# A.net
KiCad netlist of a schematic drawn in EAGLE
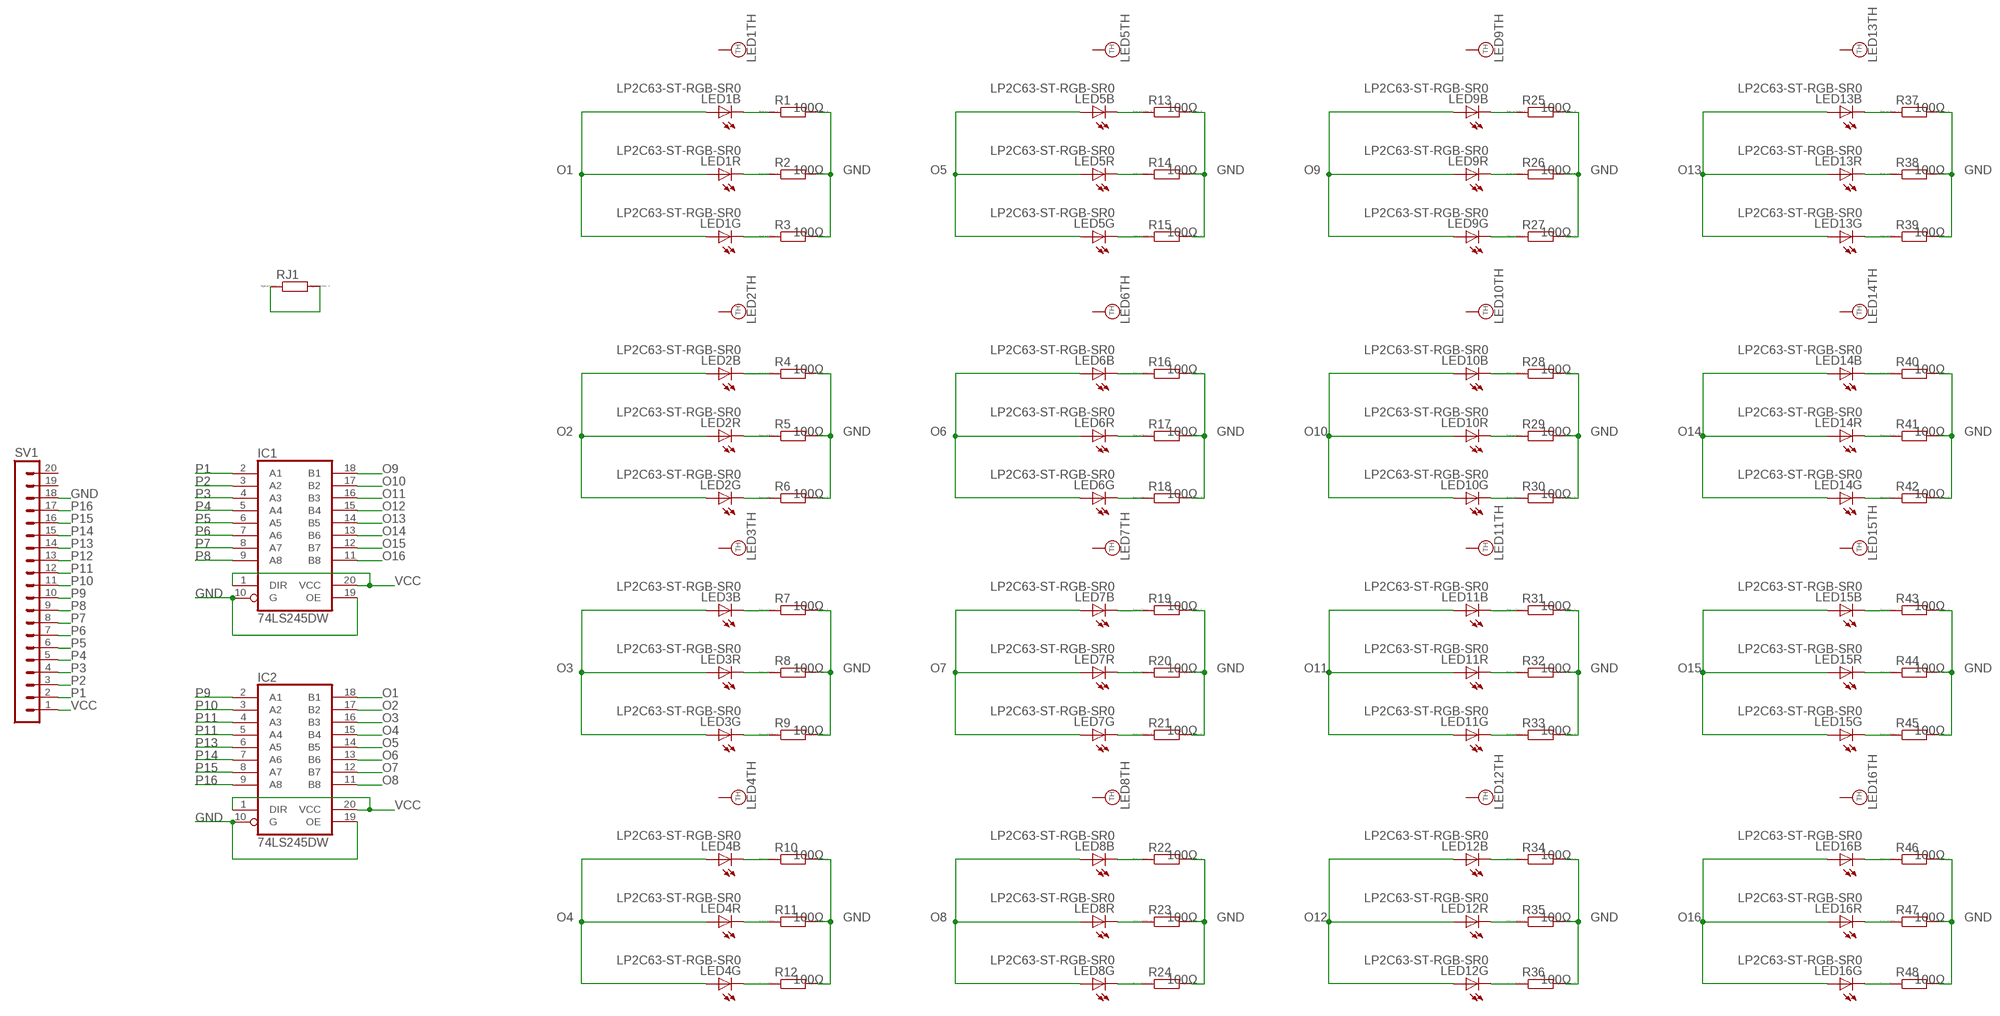
[diagram p0: schematic, sheet 1]

(export (version "E")
  (design (tool "Eeschema 10.0.6"))
  (components
    (comp (ref "IC1")
      (value "74LS245DW")
      (footprint "eagle-import:SO20W")
      (libsource (lib "eagle-import") (part "74245DWLS"))
    )
    (comp (ref "IC2")
      (value "74LS245DW")
      (footprint "eagle-import:SO20W")
      (libsource (lib "eagle-import") (part "74245DWLS"))
    )
    (comp (ref "LED1")
      (value "LP2C63-ST-RGB-SR0")
      (footprint "eagle-import:LP2C63-ST-RGB-SR0")
      (libsource (lib "eagle-import") (part "LP2C63-ST-RGB-SR0"))
    )
    (comp (ref "LED2")
      (value "LP2C63-ST-RGB-SR0")
      (footprint "eagle-import:LP2C63-ST-RGB-SR0")
      (libsource (lib "eagle-import") (part "LP2C63-ST-RGB-SR0"))
    )
    (comp (ref "LED3")
      (value "LP2C63-ST-RGB-SR0")
      (footprint "eagle-import:LP2C63-ST-RGB-SR0")
      (libsource (lib "eagle-import") (part "LP2C63-ST-RGB-SR0"))
    )
    (comp (ref "LED4")
      (value "LP2C63-ST-RGB-SR0")
      (footprint "eagle-import:LP2C63-ST-RGB-SR0")
      (libsource (lib "eagle-import") (part "LP2C63-ST-RGB-SR0"))
    )
    (comp (ref "LED5")
      (value "LP2C63-ST-RGB-SR0")
      (footprint "eagle-import:LP2C63-ST-RGB-SR0")
      (libsource (lib "eagle-import") (part "LP2C63-ST-RGB-SR0"))
    )
    (comp (ref "LED6")
      (value "LP2C63-ST-RGB-SR0")
      (footprint "eagle-import:LP2C63-ST-RGB-SR0")
      (libsource (lib "eagle-import") (part "LP2C63-ST-RGB-SR0"))
    )
    (comp (ref "LED7")
      (value "LP2C63-ST-RGB-SR0")
      (footprint "eagle-import:LP2C63-ST-RGB-SR0")
      (libsource (lib "eagle-import") (part "LP2C63-ST-RGB-SR0"))
    )
    (comp (ref "LED8")
      (value "LP2C63-ST-RGB-SR0")
      (footprint "eagle-import:LP2C63-ST-RGB-SR0")
      (libsource (lib "eagle-import") (part "LP2C63-ST-RGB-SR0"))
    )
    (comp (ref "LED9")
      (value "LP2C63-ST-RGB-SR0")
      (footprint "eagle-import:LP2C63-ST-RGB-SR0")
      (libsource (lib "eagle-import") (part "LP2C63-ST-RGB-SR0"))
    )
    (comp (ref "LED10")
      (value "LP2C63-ST-RGB-SR0")
      (footprint "eagle-import:LP2C63-ST-RGB-SR0")
      (libsource (lib "eagle-import") (part "LP2C63-ST-RGB-SR0"))
    )
    (comp (ref "LED11")
      (value "LP2C63-ST-RGB-SR0")
      (footprint "eagle-import:LP2C63-ST-RGB-SR0")
      (libsource (lib "eagle-import") (part "LP2C63-ST-RGB-SR0"))
    )
    (comp (ref "LED12")
      (value "LP2C63-ST-RGB-SR0")
      (footprint "eagle-import:LP2C63-ST-RGB-SR0")
      (libsource (lib "eagle-import") (part "LP2C63-ST-RGB-SR0"))
    )
    (comp (ref "LED13")
      (value "LP2C63-ST-RGB-SR0")
      (footprint "eagle-import:LP2C63-ST-RGB-SR0")
      (libsource (lib "eagle-import") (part "LP2C63-ST-RGB-SR0"))
    )
    (comp (ref "LED14")
      (value "LP2C63-ST-RGB-SR0")
      (footprint "eagle-import:LP2C63-ST-RGB-SR0")
      (libsource (lib "eagle-import") (part "LP2C63-ST-RGB-SR0"))
    )
    (comp (ref "LED15")
      (value "LP2C63-ST-RGB-SR0")
      (footprint "eagle-import:LP2C63-ST-RGB-SR0")
      (libsource (lib "eagle-import") (part "LP2C63-ST-RGB-SR0"))
    )
    (comp (ref "LED16")
      (value "LP2C63-ST-RGB-SR0")
      (footprint "eagle-import:LP2C63-ST-RGB-SR0")
      (libsource (lib "eagle-import") (part "LP2C63-ST-RGB-SR0"))
    )
    (comp (ref "R1")
      (value "RR0603")
      (footprint "eagle-import:R0603")
      (fields (field (name "SPICEMODEL") "NONE") (field (name "SPICEMODEL_1") "100Ω"))
      (libsource (lib "eagle-import") (part "RR0603"))
    )
    (comp (ref "R2")
      (value "RR0603")
      (footprint "eagle-import:R0603")
      (fields (field (name "SPICEMODEL") "NONE") (field (name "SPICEMODEL_1") "100Ω"))
      (libsource (lib "eagle-import") (part "RR0603"))
    )
    (comp (ref "R3")
      (value "RR0603")
      (footprint "eagle-import:R0603")
      (fields (field (name "SPICEMODEL") "NONE") (field (name "SPICEMODEL_1") "100Ω"))
      (libsource (lib "eagle-import") (part "RR0603"))
    )
    (comp (ref "R4")
      (value "RR0603")
      (footprint "eagle-import:R0603")
      (fields (field (name "SPICEMODEL") "NONE") (field (name "SPICEMODEL_1") "100Ω"))
      (libsource (lib "eagle-import") (part "RR0603"))
    )
    (comp (ref "R5")
      (value "RR0603")
      (footprint "eagle-import:R0603")
      (fields (field (name "SPICEMODEL") "NONE") (field (name "SPICEMODEL_1") "100Ω"))
      (libsource (lib "eagle-import") (part "RR0603"))
    )
    (comp (ref "R6")
      (value "RR0603")
      (footprint "eagle-import:R0603")
      (fields (field (name "SPICEMODEL") "NONE") (field (name "SPICEMODEL_1") "100Ω"))
      (libsource (lib "eagle-import") (part "RR0603"))
    )
    (comp (ref "R7")
      (value "RR0603")
      (footprint "eagle-import:R0603")
      (fields (field (name "SPICEMODEL") "NONE") (field (name "SPICEMODEL_1") "100Ω"))
      (libsource (lib "eagle-import") (part "RR0603"))
    )
    (comp (ref "R8")
      (value "RR0603")
      (footprint "eagle-import:R0603")
      (fields (field (name "SPICEMODEL") "NONE") (field (name "SPICEMODEL_1") "100Ω"))
      (libsource (lib "eagle-import") (part "RR0603"))
    )
    (comp (ref "R9")
      (value "RR0603")
      (footprint "eagle-import:R0603")
      (fields (field (name "SPICEMODEL") "NONE") (field (name "SPICEMODEL_1") "100Ω"))
      (libsource (lib "eagle-import") (part "RR0603"))
    )
    (comp (ref "R10")
      (value "RR0603")
      (footprint "eagle-import:R0603")
      (fields (field (name "SPICEMODEL") "NONE") (field (name "SPICEMODEL_1") "100Ω"))
      (libsource (lib "eagle-import") (part "RR0603"))
    )
    (comp (ref "R11")
      (value "RR0603")
      (footprint "eagle-import:R0603")
      (fields (field (name "SPICEMODEL") "NONE") (field (name "SPICEMODEL_1") "100Ω"))
      (libsource (lib "eagle-import") (part "RR0603"))
    )
    (comp (ref "R12")
      (value "RR0603")
      (footprint "eagle-import:R0603")
      (fields (field (name "SPICEMODEL") "NONE") (field (name "SPICEMODEL_1") "100Ω"))
      (libsource (lib "eagle-import") (part "RR0603"))
    )
    (comp (ref "R13")
      (value "RR0603")
      (footprint "eagle-import:R0603")
      (fields (field (name "SPICEMODEL") "NONE") (field (name "SPICEMODEL_1") "100Ω"))
      (libsource (lib "eagle-import") (part "RR0603"))
    )
    (comp (ref "R14")
      (value "RR0603")
      (footprint "eagle-import:R0603")
      (fields (field (name "SPICEMODEL") "NONE") (field (name "SPICEMODEL_1") "100Ω"))
      (libsource (lib "eagle-import") (part "RR0603"))
    )
    (comp (ref "R15")
      (value "RR0603")
      (footprint "eagle-import:R0603")
      (fields (field (name "SPICEMODEL") "NONE") (field (name "SPICEMODEL_1") "100Ω"))
      (libsource (lib "eagle-import") (part "RR0603"))
    )
    (comp (ref "R16")
      (value "RR0603")
      (footprint "eagle-import:R0603")
      (fields (field (name "SPICEMODEL") "NONE") (field (name "SPICEMODEL_1") "100Ω"))
      (libsource (lib "eagle-import") (part "RR0603"))
    )
    (comp (ref "R17")
      (value "RR0603")
      (footprint "eagle-import:R0603")
      (fields (field (name "SPICEMODEL") "NONE") (field (name "SPICEMODEL_1") "100Ω"))
      (libsource (lib "eagle-import") (part "RR0603"))
    )
    (comp (ref "R18")
      (value "RR0603")
      (footprint "eagle-import:R0603")
      (fields (field (name "SPICEMODEL") "NONE") (field (name "SPICEMODEL_1") "100Ω"))
      (libsource (lib "eagle-import") (part "RR0603"))
    )
    (comp (ref "R19")
      (value "RR0603")
      (footprint "eagle-import:R0603")
      (fields (field (name "SPICEMODEL") "NONE") (field (name "SPICEMODEL_1") "100Ω"))
      (libsource (lib "eagle-import") (part "RR0603"))
    )
    (comp (ref "R20")
      (value "RR0603")
      (footprint "eagle-import:R0603")
      (fields (field (name "SPICEMODEL") "NONE") (field (name "SPICEMODEL_1") "100Ω"))
      (libsource (lib "eagle-import") (part "RR0603"))
    )
    (comp (ref "R21")
      (value "RR0603")
      (footprint "eagle-import:R0603")
      (fields (field (name "SPICEMODEL") "NONE") (field (name "SPICEMODEL_1") "100Ω"))
      (libsource (lib "eagle-import") (part "RR0603"))
    )
    (comp (ref "R22")
      (value "RR0603")
      (footprint "eagle-import:R0603")
      (fields (field (name "SPICEMODEL") "NONE") (field (name "SPICEMODEL_1") "100Ω"))
      (libsource (lib "eagle-import") (part "RR0603"))
    )
    (comp (ref "R23")
      (value "RR0603")
      (footprint "eagle-import:R0603")
      (fields (field (name "SPICEMODEL") "NONE") (field (name "SPICEMODEL_1") "100Ω"))
      (libsource (lib "eagle-import") (part "RR0603"))
    )
    (comp (ref "R24")
      (value "RR0603")
      (footprint "eagle-import:R0603")
      (fields (field (name "SPICEMODEL") "NONE") (field (name "SPICEMODEL_1") "100Ω"))
      (libsource (lib "eagle-import") (part "RR0603"))
    )
    (comp (ref "R25")
      (value "RR0603")
      (footprint "eagle-import:R0603")
      (fields (field (name "SPICEMODEL") "NONE") (field (name "SPICEMODEL_1") "100Ω"))
      (libsource (lib "eagle-import") (part "RR0603"))
    )
    (comp (ref "R26")
      (value "RR0603")
      (footprint "eagle-import:R0603")
      (fields (field (name "SPICEMODEL") "NONE") (field (name "SPICEMODEL_1") "100Ω"))
      (libsource (lib "eagle-import") (part "RR0603"))
    )
    (comp (ref "R27")
      (value "RR0603")
      (footprint "eagle-import:R0603")
      (fields (field (name "SPICEMODEL") "NONE") (field (name "SPICEMODEL_1") "100Ω"))
      (libsource (lib "eagle-import") (part "RR0603"))
    )
    (comp (ref "R28")
      (value "RR0603")
      (footprint "eagle-import:R0603")
      (fields (field (name "SPICEMODEL") "NONE") (field (name "SPICEMODEL_1") "100Ω"))
      (libsource (lib "eagle-import") (part "RR0603"))
    )
    (comp (ref "R29")
      (value "RR0603")
      (footprint "eagle-import:R0603")
      (fields (field (name "SPICEMODEL") "NONE") (field (name "SPICEMODEL_1") "100Ω"))
      (libsource (lib "eagle-import") (part "RR0603"))
    )
    (comp (ref "R30")
      (value "RR0603")
      (footprint "eagle-import:R0603")
      (fields (field (name "SPICEMODEL") "NONE") (field (name "SPICEMODEL_1") "100Ω"))
      (libsource (lib "eagle-import") (part "RR0603"))
    )
    (comp (ref "R31")
      (value "RR0603")
      (footprint "eagle-import:R0603")
      (fields (field (name "SPICEMODEL") "NONE") (field (name "SPICEMODEL_1") "100Ω"))
      (libsource (lib "eagle-import") (part "RR0603"))
    )
    (comp (ref "R32")
      (value "RR0603")
      (footprint "eagle-import:R0603")
      (fields (field (name "SPICEMODEL") "NONE") (field (name "SPICEMODEL_1") "100Ω"))
      (libsource (lib "eagle-import") (part "RR0603"))
    )
    (comp (ref "R33")
      (value "RR0603")
      (footprint "eagle-import:R0603")
      (fields (field (name "SPICEMODEL") "NONE") (field (name "SPICEMODEL_1") "100Ω"))
      (libsource (lib "eagle-import") (part "RR0603"))
    )
    (comp (ref "R34")
      (value "RR0603")
      (footprint "eagle-import:R0603")
      (fields (field (name "SPICEMODEL") "NONE") (field (name "SPICEMODEL_1") "100Ω"))
      (libsource (lib "eagle-import") (part "RR0603"))
    )
    (comp (ref "R35")
      (value "RR0603")
      (footprint "eagle-import:R0603")
      (fields (field (name "SPICEMODEL") "NONE") (field (name "SPICEMODEL_1") "100Ω"))
      (libsource (lib "eagle-import") (part "RR0603"))
    )
    (comp (ref "R36")
      (value "RR0603")
      (footprint "eagle-import:R0603")
      (fields (field (name "SPICEMODEL") "NONE") (field (name "SPICEMODEL_1") "100Ω"))
      (libsource (lib "eagle-import") (part "RR0603"))
    )
    (comp (ref "R37")
      (value "RR0603")
      (footprint "eagle-import:R0603")
      (fields (field (name "SPICEMODEL") "NONE") (field (name "SPICEMODEL_1") "100Ω"))
      (libsource (lib "eagle-import") (part "RR0603"))
    )
    (comp (ref "R38")
      (value "RR0603")
      (footprint "eagle-import:R0603")
      (fields (field (name "SPICEMODEL") "NONE") (field (name "SPICEMODEL_1") "100Ω"))
      (libsource (lib "eagle-import") (part "RR0603"))
    )
    (comp (ref "R39")
      (value "RR0603")
      (footprint "eagle-import:R0603")
      (fields (field (name "SPICEMODEL") "NONE") (field (name "SPICEMODEL_1") "100Ω"))
      (libsource (lib "eagle-import") (part "RR0603"))
    )
    (comp (ref "R40")
      (value "RR0603")
      (footprint "eagle-import:R0603")
      (fields (field (name "SPICEMODEL") "NONE") (field (name "SPICEMODEL_1") "100Ω"))
      (libsource (lib "eagle-import") (part "RR0603"))
    )
    (comp (ref "R41")
      (value "RR0603")
      (footprint "eagle-import:R0603")
      (fields (field (name "SPICEMODEL") "NONE") (field (name "SPICEMODEL_1") "100Ω"))
      (libsource (lib "eagle-import") (part "RR0603"))
    )
    (comp (ref "R42")
      (value "RR0603")
      (footprint "eagle-import:R0603")
      (fields (field (name "SPICEMODEL") "NONE") (field (name "SPICEMODEL_1") "100Ω"))
      (libsource (lib "eagle-import") (part "RR0603"))
    )
    (comp (ref "R43")
      (value "RR0603")
      (footprint "eagle-import:R0603")
      (fields (field (name "SPICEMODEL") "NONE") (field (name "SPICEMODEL_1") "100Ω"))
      (libsource (lib "eagle-import") (part "RR0603"))
    )
    (comp (ref "R44")
      (value "RR0603")
      (footprint "eagle-import:R0603")
      (fields (field (name "SPICEMODEL") "NONE") (field (name "SPICEMODEL_1") "100Ω"))
      (libsource (lib "eagle-import") (part "RR0603"))
    )
    (comp (ref "R45")
      (value "RR0603")
      (footprint "eagle-import:R0603")
      (fields (field (name "SPICEMODEL") "NONE") (field (name "SPICEMODEL_1") "100Ω"))
      (libsource (lib "eagle-import") (part "RR0603"))
    )
    (comp (ref "R46")
      (value "RR0603")
      (footprint "eagle-import:R0603")
      (fields (field (name "SPICEMODEL") "NONE") (field (name "SPICEMODEL_1") "100Ω"))
      (libsource (lib "eagle-import") (part "RR0603"))
    )
    (comp (ref "R47")
      (value "RR0603")
      (footprint "eagle-import:R0603")
      (fields (field (name "SPICEMODEL") "NONE") (field (name "SPICEMODEL_1") "100Ω"))
      (libsource (lib "eagle-import") (part "RR0603"))
    )
    (comp (ref "R48")
      (value "RR0603")
      (footprint "eagle-import:R0603")
      (fields (field (name "SPICEMODEL") "NONE") (field (name "SPICEMODEL_1") "100Ω"))
      (libsource (lib "eagle-import") (part "RR0603"))
    )
    (comp (ref "RJ1")
      (value "R")
      (footprint "eagle-import:R0805")
      (libsource (lib "eagle-import") (part "R"))
    )
    (comp (ref "SV1")
      (value "MA20-1")
      (footprint "eagle-import:MA20-1")
      (libsource (lib "eagle-import") (part "MA20-1"))
    )
  )
  (nets
    (net (code "1") (name "/GND") (class "Default")
      (node (ref "IC1") (pin "10") (pinfunction "G_10") (pintype "input"))
      (node (ref "IC1") (pin "19") (pinfunction "OE_19") (pintype "bidirectional"))
      (node (ref "IC2") (pin "10") (pinfunction "G_10") (pintype "input"))
      (node (ref "IC2") (pin "19") (pinfunction "OE_19") (pintype "bidirectional"))
      (node (ref "R1") (pin "2") (pinfunction "2_2") (pintype "passive"))
      (node (ref "R10") (pin "2") (pinfunction "2_2") (pintype "passive"))
      (node (ref "R11") (pin "2") (pinfunction "2_2") (pintype "passive"))
      (node (ref "R12") (pin "2") (pinfunction "2_2") (pintype "passive"))
      (node (ref "R13") (pin "2") (pinfunction "2_2") (pintype "passive"))
      (node (ref "R14") (pin "2") (pinfunction "2_2") (pintype "passive"))
      (node (ref "R15") (pin "2") (pinfunction "2_2") (pintype "passive"))
      (node (ref "R16") (pin "2") (pinfunction "2_2") (pintype "passive"))
      (node (ref "R17") (pin "2") (pinfunction "2_2") (pintype "passive"))
      (node (ref "R18") (pin "2") (pinfunction "2_2") (pintype "passive"))
      (node (ref "R19") (pin "2") (pinfunction "2_2") (pintype "passive"))
      (node (ref "R2") (pin "2") (pinfunction "2_2") (pintype "passive"))
      (node (ref "R20") (pin "2") (pinfunction "2_2") (pintype "passive"))
      (node (ref "R21") (pin "2") (pinfunction "2_2") (pintype "passive"))
      (node (ref "R22") (pin "2") (pinfunction "2_2") (pintype "passive"))
      (node (ref "R23") (pin "2") (pinfunction "2_2") (pintype "passive"))
      (node (ref "R24") (pin "2") (pinfunction "2_2") (pintype "passive"))
      (node (ref "R25") (pin "2") (pinfunction "2_2") (pintype "passive"))
      (node (ref "R26") (pin "2") (pinfunction "2_2") (pintype "passive"))
      (node (ref "R27") (pin "2") (pinfunction "2_2") (pintype "passive"))
      (node (ref "R28") (pin "2") (pinfunction "2_2") (pintype "passive"))
      (node (ref "R29") (pin "2") (pinfunction "2_2") (pintype "passive"))
      (node (ref "R3") (pin "2") (pinfunction "2_2") (pintype "passive"))
      (node (ref "R30") (pin "2") (pinfunction "2_2") (pintype "passive"))
      (node (ref "R31") (pin "2") (pinfunction "2_2") (pintype "passive"))
      (node (ref "R32") (pin "2") (pinfunction "2_2") (pintype "passive"))
      (node (ref "R33") (pin "2") (pinfunction "2_2") (pintype "passive"))
      (node (ref "R34") (pin "2") (pinfunction "2_2") (pintype "passive"))
      (node (ref "R35") (pin "2") (pinfunction "2_2") (pintype "passive"))
      (node (ref "R36") (pin "2") (pinfunction "2_2") (pintype "passive"))
      (node (ref "R37") (pin "2") (pinfunction "2_2") (pintype "passive"))
      (node (ref "R38") (pin "2") (pinfunction "2_2") (pintype "passive"))
      (node (ref "R39") (pin "2") (pinfunction "2_2") (pintype "passive"))
      (node (ref "R4") (pin "2") (pinfunction "2_2") (pintype "passive"))
      (node (ref "R40") (pin "2") (pinfunction "2_2") (pintype "passive"))
      (node (ref "R41") (pin "2") (pinfunction "2_2") (pintype "passive"))
      (node (ref "R42") (pin "2") (pinfunction "2_2") (pintype "passive"))
      (node (ref "R43") (pin "2") (pinfunction "2_2") (pintype "passive"))
      (node (ref "R44") (pin "2") (pinfunction "2_2") (pintype "passive"))
      (node (ref "R45") (pin "2") (pinfunction "2_2") (pintype "passive"))
      (node (ref "R46") (pin "2") (pinfunction "2_2") (pintype "passive"))
      (node (ref "R47") (pin "2") (pinfunction "2_2") (pintype "passive"))
      (node (ref "R48") (pin "2") (pinfunction "2_2") (pintype "passive"))
      (node (ref "R5") (pin "2") (pinfunction "2_2") (pintype "passive"))
      (node (ref "R6") (pin "2") (pinfunction "2_2") (pintype "passive"))
      (node (ref "R7") (pin "2") (pinfunction "2_2") (pintype "passive"))
      (node (ref "R8") (pin "2") (pinfunction "2_2") (pintype "passive"))
      (node (ref "R9") (pin "2") (pinfunction "2_2") (pintype "passive"))
      (node (ref "RJ1") (pin "1") (pinfunction "1_1") (pintype "passive"))
      (node (ref "RJ1") (pin "2") (pinfunction "2_2") (pintype "passive"))
      (node (ref "SV1") (pin "18") (pinfunction "18_18") (pintype "passive"))
    )
    (net (code "2") (name "/O1") (class "Default")
      (node (ref "IC2") (pin "18") (pinfunction "B1_18") (pintype "bidirectional"))
      (node (ref "LED1") (pin "1") (pinfunction "A_1") (pintype "passive"))
      (node (ref "LED1") (pin "2") (pinfunction "A_2") (pintype "passive"))
      (node (ref "LED1") (pin "3") (pinfunction "A_3") (pintype "passive"))
    )
    (net (code "3") (name "/O2") (class "Default")
      (node (ref "IC2") (pin "17") (pinfunction "B2_17") (pintype "bidirectional"))
      (node (ref "LED2") (pin "1") (pinfunction "A_1") (pintype "passive"))
      (node (ref "LED2") (pin "2") (pinfunction "A_2") (pintype "passive"))
      (node (ref "LED2") (pin "3") (pinfunction "A_3") (pintype "passive"))
    )
    (net (code "4") (name "/O3") (class "Default")
      (node (ref "IC2") (pin "16") (pinfunction "B3_16") (pintype "bidirectional"))
      (node (ref "LED3") (pin "1") (pinfunction "A_1") (pintype "passive"))
      (node (ref "LED3") (pin "2") (pinfunction "A_2") (pintype "passive"))
      (node (ref "LED3") (pin "3") (pinfunction "A_3") (pintype "passive"))
    )
    (net (code "5") (name "/O4") (class "Default")
      (node (ref "IC2") (pin "15") (pinfunction "B4_15") (pintype "bidirectional"))
      (node (ref "LED4") (pin "1") (pinfunction "A_1") (pintype "passive"))
      (node (ref "LED4") (pin "2") (pinfunction "A_2") (pintype "passive"))
      (node (ref "LED4") (pin "3") (pinfunction "A_3") (pintype "passive"))
    )
    (net (code "6") (name "/O5") (class "Default")
      (node (ref "IC2") (pin "14") (pinfunction "B5_14") (pintype "bidirectional"))
      (node (ref "LED5") (pin "1") (pinfunction "A_1") (pintype "passive"))
      (node (ref "LED5") (pin "2") (pinfunction "A_2") (pintype "passive"))
      (node (ref "LED5") (pin "3") (pinfunction "A_3") (pintype "passive"))
    )
    (net (code "7") (name "/O6") (class "Default")
      (node (ref "IC2") (pin "13") (pinfunction "B6_13") (pintype "bidirectional"))
      (node (ref "LED6") (pin "1") (pinfunction "A_1") (pintype "passive"))
      (node (ref "LED6") (pin "2") (pinfunction "A_2") (pintype "passive"))
      (node (ref "LED6") (pin "3") (pinfunction "A_3") (pintype "passive"))
    )
    (net (code "8") (name "/O7") (class "Default")
      (node (ref "IC2") (pin "12") (pinfunction "B7_12") (pintype "bidirectional"))
      (node (ref "LED7") (pin "1") (pinfunction "A_1") (pintype "passive"))
      (node (ref "LED7") (pin "2") (pinfunction "A_2") (pintype "passive"))
      (node (ref "LED7") (pin "3") (pinfunction "A_3") (pintype "passive"))
    )
    (net (code "9") (name "/O8") (class "Default")
      (node (ref "IC2") (pin "11") (pinfunction "B8_11") (pintype "bidirectional"))
      (node (ref "LED8") (pin "1") (pinfunction "A_1") (pintype "passive"))
      (node (ref "LED8") (pin "2") (pinfunction "A_2") (pintype "passive"))
      (node (ref "LED8") (pin "3") (pinfunction "A_3") (pintype "passive"))
    )
    (net (code "10") (name "/O9") (class "Default")
      (node (ref "IC1") (pin "18") (pinfunction "B1_18") (pintype "bidirectional"))
      (node (ref "LED9") (pin "1") (pinfunction "A_1") (pintype "passive"))
      (node (ref "LED9") (pin "2") (pinfunction "A_2") (pintype "passive"))
      (node (ref "LED9") (pin "3") (pinfunction "A_3") (pintype "passive"))
    )
    (net (code "11") (name "/O10") (class "Default")
      (node (ref "IC1") (pin "17") (pinfunction "B2_17") (pintype "bidirectional"))
      (node (ref "LED10") (pin "1") (pinfunction "A_1") (pintype "passive"))
      (node (ref "LED10") (pin "2") (pinfunction "A_2") (pintype "passive"))
      (node (ref "LED10") (pin "3") (pinfunction "A_3") (pintype "passive"))
    )
    (net (code "12") (name "/O11") (class "Default")
      (node (ref "IC1") (pin "16") (pinfunction "B3_16") (pintype "bidirectional"))
      (node (ref "LED11") (pin "1") (pinfunction "A_1") (pintype "passive"))
      (node (ref "LED11") (pin "2") (pinfunction "A_2") (pintype "passive"))
      (node (ref "LED11") (pin "3") (pinfunction "A_3") (pintype "passive"))
    )
    (net (code "13") (name "/O12") (class "Default")
      (node (ref "IC1") (pin "15") (pinfunction "B4_15") (pintype "bidirectional"))
      (node (ref "LED12") (pin "1") (pinfunction "A_1") (pintype "passive"))
      (node (ref "LED12") (pin "2") (pinfunction "A_2") (pintype "passive"))
      (node (ref "LED12") (pin "3") (pinfunction "A_3") (pintype "passive"))
    )
    (net (code "14") (name "/O13") (class "Default")
      (node (ref "IC1") (pin "14") (pinfunction "B5_14") (pintype "bidirectional"))
      (node (ref "LED13") (pin "1") (pinfunction "A_1") (pintype "passive"))
      (node (ref "LED13") (pin "2") (pinfunction "A_2") (pintype "passive"))
      (node (ref "LED13") (pin "3") (pinfunction "A_3") (pintype "passive"))
    )
    (net (code "15") (name "/O14") (class "Default")
      (node (ref "IC1") (pin "13") (pinfunction "B6_13") (pintype "bidirectional"))
      (node (ref "LED14") (pin "1") (pinfunction "A_1") (pintype "passive"))
      (node (ref "LED14") (pin "2") (pinfunction "A_2") (pintype "passive"))
      (node (ref "LED14") (pin "3") (pinfunction "A_3") (pintype "passive"))
    )
    (net (code "16") (name "/O15") (class "Default")
      (node (ref "IC1") (pin "12") (pinfunction "B7_12") (pintype "bidirectional"))
      (node (ref "LED15") (pin "1") (pinfunction "A_1") (pintype "passive"))
      (node (ref "LED15") (pin "2") (pinfunction "A_2") (pintype "passive"))
      (node (ref "LED15") (pin "3") (pinfunction "A_3") (pintype "passive"))
    )
    (net (code "17") (name "/O16") (class "Default")
      (node (ref "IC1") (pin "11") (pinfunction "B8_11") (pintype "bidirectional"))
      (node (ref "LED16") (pin "1") (pinfunction "A_1") (pintype "passive"))
      (node (ref "LED16") (pin "2") (pinfunction "A_2") (pintype "passive"))
      (node (ref "LED16") (pin "3") (pinfunction "A_3") (pintype "passive"))
    )
    (net (code "18") (name "/P1") (class "Default")
      (node (ref "IC1") (pin "2") (pinfunction "A1_2") (pintype "bidirectional"))
      (node (ref "SV1") (pin "2") (pinfunction "2_2") (pintype "passive"))
    )
    (net (code "19") (name "/P2") (class "Default")
      (node (ref "IC1") (pin "3") (pinfunction "A2_3") (pintype "bidirectional"))
      (node (ref "SV1") (pin "3") (pinfunction "3_3") (pintype "passive"))
    )
    (net (code "20") (name "/P3") (class "Default")
      (node (ref "IC1") (pin "4") (pinfunction "A3_4") (pintype "bidirectional"))
      (node (ref "SV1") (pin "4") (pinfunction "4_4") (pintype "passive"))
    )
    (net (code "21") (name "/P4") (class "Default")
      (node (ref "IC1") (pin "5") (pinfunction "A4_5") (pintype "bidirectional"))
      (node (ref "SV1") (pin "5") (pinfunction "5_5") (pintype "passive"))
    )
    (net (code "22") (name "/P5") (class "Default")
      (node (ref "IC1") (pin "6") (pinfunction "A5_6") (pintype "bidirectional"))
      (node (ref "SV1") (pin "6") (pinfunction "6_6") (pintype "passive"))
    )
    (net (code "23") (name "/P6") (class "Default")
      (node (ref "IC1") (pin "7") (pinfunction "A6_7") (pintype "bidirectional"))
      (node (ref "SV1") (pin "7") (pinfunction "7_7") (pintype "passive"))
    )
    (net (code "24") (name "/P7") (class "Default")
      (node (ref "IC1") (pin "8") (pinfunction "A7_8") (pintype "bidirectional"))
      (node (ref "SV1") (pin "8") (pinfunction "8_8") (pintype "passive"))
    )
    (net (code "25") (name "/P8") (class "Default")
      (node (ref "IC1") (pin "9") (pinfunction "A8_9") (pintype "bidirectional"))
      (node (ref "SV1") (pin "9") (pinfunction "9_9") (pintype "passive"))
    )
    (net (code "26") (name "/P9") (class "Default")
      (node (ref "IC2") (pin "2") (pinfunction "A1_2") (pintype "bidirectional"))
      (node (ref "SV1") (pin "10") (pinfunction "10_10") (pintype "passive"))
    )
    (net (code "27") (name "/P10") (class "Default")
      (node (ref "IC2") (pin "3") (pinfunction "A2_3") (pintype "bidirectional"))
      (node (ref "SV1") (pin "11") (pinfunction "11_11") (pintype "passive"))
    )
    (net (code "28") (name "/P11") (class "Default")
      (node (ref "IC2") (pin "4") (pinfunction "A3_4") (pintype "bidirectional"))
      (node (ref "SV1") (pin "12") (pinfunction "12_12") (pintype "passive"))
    )
    (net (code "29") (name "/P12") (class "Default")
      (node (ref "IC2") (pin "5") (pinfunction "A4_5") (pintype "bidirectional"))
      (node (ref "SV1") (pin "13") (pinfunction "13_13") (pintype "passive"))
    )
    (net (code "30") (name "/P13") (class "Default")
      (node (ref "IC2") (pin "6") (pinfunction "A5_6") (pintype "bidirectional"))
      (node (ref "SV1") (pin "14") (pinfunction "14_14") (pintype "passive"))
    )
    (net (code "31") (name "/P14") (class "Default")
      (node (ref "IC2") (pin "7") (pinfunction "A6_7") (pintype "bidirectional"))
      (node (ref "SV1") (pin "15") (pinfunction "15_15") (pintype "passive"))
    )
    (net (code "32") (name "/P15") (class "Default")
      (node (ref "IC2") (pin "8") (pinfunction "A7_8") (pintype "bidirectional"))
      (node (ref "SV1") (pin "16") (pinfunction "16_16") (pintype "passive"))
    )
    (net (code "33") (name "/P16") (class "Default")
      (node (ref "IC2") (pin "9") (pinfunction "A8_9") (pintype "bidirectional"))
      (node (ref "SV1") (pin "17") (pinfunction "17_17") (pintype "passive"))
    )
    (net (code "34") (name "/VCC") (class "Default")
      (node (ref "IC1") (pin "1") (pinfunction "DIR_1") (pintype "input"))
      (node (ref "IC1") (pin "20") (pinfunction "VCC_20") (pintype "bidirectional"))
      (node (ref "IC2") (pin "1") (pinfunction "DIR_1") (pintype "input"))
      (node (ref "IC2") (pin "20") (pinfunction "VCC_20") (pintype "bidirectional"))
      (node (ref "SV1") (pin "1") (pinfunction "1_1") (pintype "passive"))
    )
    (net (code "35") (name "Net-(LED1A-C)") (class "Default")
      (node (ref "LED1") (pin "4") (pinfunction "C_4") (pintype "passive"))
      (node (ref "R1") (pin "1") (pinfunction "1_1") (pintype "passive"))
    )
    (net (code "36") (name "Net-(LED1B-C)") (class "Default")
      (node (ref "LED1") (pin "6") (pinfunction "C_6") (pintype "passive"))
      (node (ref "R3") (pin "1") (pinfunction "1_1") (pintype "passive"))
    )
    (net (code "37") (name "Net-(LED1C-C)") (class "Default")
      (node (ref "LED1") (pin "5") (pinfunction "C_5") (pintype "passive"))
      (node (ref "R2") (pin "1") (pinfunction "1_1") (pintype "passive"))
    )
    (net (code "38") (name "Net-(LED2A-C)") (class "Default")
      (node (ref "LED2") (pin "4") (pinfunction "C_4") (pintype "passive"))
      (node (ref "R4") (pin "1") (pinfunction "1_1") (pintype "passive"))
    )
    (net (code "39") (name "Net-(LED2B-C)") (class "Default")
      (node (ref "LED2") (pin "6") (pinfunction "C_6") (pintype "passive"))
      (node (ref "R6") (pin "1") (pinfunction "1_1") (pintype "passive"))
    )
    (net (code "40") (name "Net-(LED2C-C)") (class "Default")
      (node (ref "LED2") (pin "5") (pinfunction "C_5") (pintype "passive"))
      (node (ref "R5") (pin "1") (pinfunction "1_1") (pintype "passive"))
    )
    (net (code "41") (name "Net-(LED3A-C)") (class "Default")
      (node (ref "LED3") (pin "4") (pinfunction "C_4") (pintype "passive"))
      (node (ref "R7") (pin "1") (pinfunction "1_1") (pintype "passive"))
    )
    (net (code "42") (name "Net-(LED3B-C)") (class "Default")
      (node (ref "LED3") (pin "6") (pinfunction "C_6") (pintype "passive"))
      (node (ref "R9") (pin "1") (pinfunction "1_1") (pintype "passive"))
    )
    (net (code "43") (name "Net-(LED3C-C)") (class "Default")
      (node (ref "LED3") (pin "5") (pinfunction "C_5") (pintype "passive"))
      (node (ref "R8") (pin "1") (pinfunction "1_1") (pintype "passive"))
    )
    (net (code "44") (name "Net-(LED4A-C)") (class "Default")
      (node (ref "LED4") (pin "4") (pinfunction "C_4") (pintype "passive"))
      (node (ref "R10") (pin "1") (pinfunction "1_1") (pintype "passive"))
    )
    (net (code "45") (name "Net-(LED4B-C)") (class "Default")
      (node (ref "LED4") (pin "6") (pinfunction "C_6") (pintype "passive"))
      (node (ref "R12") (pin "1") (pinfunction "1_1") (pintype "passive"))
    )
    (net (code "46") (name "Net-(LED4C-C)") (class "Default")
      (node (ref "LED4") (pin "5") (pinfunction "C_5") (pintype "passive"))
      (node (ref "R11") (pin "1") (pinfunction "1_1") (pintype "passive"))
    )
    (net (code "47") (name "Net-(LED5A-C)") (class "Default")
      (node (ref "LED5") (pin "4") (pinfunction "C_4") (pintype "passive"))
      (node (ref "R13") (pin "1") (pinfunction "1_1") (pintype "passive"))
    )
    (net (code "48") (name "Net-(LED5B-C)") (class "Default")
      (node (ref "LED5") (pin "6") (pinfunction "C_6") (pintype "passive"))
      (node (ref "R15") (pin "1") (pinfunction "1_1") (pintype "passive"))
    )
    (net (code "49") (name "Net-(LED5C-C)") (class "Default")
      (node (ref "LED5") (pin "5") (pinfunction "C_5") (pintype "passive"))
      (node (ref "R14") (pin "1") (pinfunction "1_1") (pintype "passive"))
    )
    (net (code "50") (name "Net-(LED6A-C)") (class "Default")
      (node (ref "LED6") (pin "4") (pinfunction "C_4") (pintype "passive"))
      (node (ref "R16") (pin "1") (pinfunction "1_1") (pintype "passive"))
    )
    (net (code "51") (name "Net-(LED6B-C)") (class "Default")
      (node (ref "LED6") (pin "6") (pinfunction "C_6") (pintype "passive"))
      (node (ref "R18") (pin "1") (pinfunction "1_1") (pintype "passive"))
    )
    (net (code "52") (name "Net-(LED6C-C)") (class "Default")
      (node (ref "LED6") (pin "5") (pinfunction "C_5") (pintype "passive"))
      (node (ref "R17") (pin "1") (pinfunction "1_1") (pintype "passive"))
    )
    (net (code "53") (name "Net-(LED7A-C)") (class "Default")
      (node (ref "LED7") (pin "4") (pinfunction "C_4") (pintype "passive"))
      (node (ref "R19") (pin "1") (pinfunction "1_1") (pintype "passive"))
    )
    (net (code "54") (name "Net-(LED7B-C)") (class "Default")
      (node (ref "LED7") (pin "6") (pinfunction "C_6") (pintype "passive"))
      (node (ref "R21") (pin "1") (pinfunction "1_1") (pintype "passive"))
    )
    (net (code "55") (name "Net-(LED7C-C)") (class "Default")
      (node (ref "LED7") (pin "5") (pinfunction "C_5") (pintype "passive"))
      (node (ref "R20") (pin "1") (pinfunction "1_1") (pintype "passive"))
    )
    (net (code "56") (name "Net-(LED8A-C)") (class "Default")
      (node (ref "LED8") (pin "4") (pinfunction "C_4") (pintype "passive"))
      (node (ref "R22") (pin "1") (pinfunction "1_1") (pintype "passive"))
    )
    (net (code "57") (name "Net-(LED8B-C)") (class "Default")
      (node (ref "LED8") (pin "6") (pinfunction "C_6") (pintype "passive"))
      (node (ref "R24") (pin "1") (pinfunction "1_1") (pintype "passive"))
    )
    (net (code "58") (name "Net-(LED8C-C)") (class "Default")
      (node (ref "LED8") (pin "5") (pinfunction "C_5") (pintype "passive"))
      (node (ref "R23") (pin "1") (pinfunction "1_1") (pintype "passive"))
    )
    (net (code "59") (name "Net-(LED9A-C)") (class "Default")
      (node (ref "LED9") (pin "4") (pinfunction "C_4") (pintype "passive"))
      (node (ref "R25") (pin "1") (pinfunction "1_1") (pintype "passive"))
    )
    (net (code "60") (name "Net-(LED9B-C)") (class "Default")
      (node (ref "LED9") (pin "6") (pinfunction "C_6") (pintype "passive"))
      (node (ref "R27") (pin "1") (pinfunction "1_1") (pintype "passive"))
    )
    (net (code "61") (name "Net-(LED9C-C)") (class "Default")
      (node (ref "LED9") (pin "5") (pinfunction "C_5") (pintype "passive"))
      (node (ref "R26") (pin "1") (pinfunction "1_1") (pintype "passive"))
    )
    (net (code "62") (name "Net-(LED10A-C)") (class "Default")
      (node (ref "LED10") (pin "4") (pinfunction "C_4") (pintype "passive"))
      (node (ref "R28") (pin "1") (pinfunction "1_1") (pintype "passive"))
    )
    (net (code "63") (name "Net-(LED10B-C)") (class "Default")
      (node (ref "LED10") (pin "6") (pinfunction "C_6") (pintype "passive"))
      (node (ref "R30") (pin "1") (pinfunction "1_1") (pintype "passive"))
    )
    (net (code "64") (name "Net-(LED10C-C)") (class "Default")
      (node (ref "LED10") (pin "5") (pinfunction "C_5") (pintype "passive"))
      (node (ref "R29") (pin "1") (pinfunction "1_1") (pintype "passive"))
    )
    (net (code "65") (name "Net-(LED11A-C)") (class "Default")
      (node (ref "LED11") (pin "4") (pinfunction "C_4") (pintype "passive"))
      (node (ref "R31") (pin "1") (pinfunction "1_1") (pintype "passive"))
    )
    (net (code "66") (name "Net-(LED11B-C)") (class "Default")
      (node (ref "LED11") (pin "6") (pinfunction "C_6") (pintype "passive"))
      (node (ref "R33") (pin "1") (pinfunction "1_1") (pintype "passive"))
    )
    (net (code "67") (name "Net-(LED11C-C)") (class "Default")
      (node (ref "LED11") (pin "5") (pinfunction "C_5") (pintype "passive"))
      (node (ref "R32") (pin "1") (pinfunction "1_1") (pintype "passive"))
    )
    (net (code "68") (name "Net-(LED12A-C)") (class "Default")
      (node (ref "LED12") (pin "4") (pinfunction "C_4") (pintype "passive"))
      (node (ref "R34") (pin "1") (pinfunction "1_1") (pintype "passive"))
    )
    (net (code "69") (name "Net-(LED12B-C)") (class "Default")
      (node (ref "LED12") (pin "6") (pinfunction "C_6") (pintype "passive"))
      (node (ref "R36") (pin "1") (pinfunction "1_1") (pintype "passive"))
    )
    (net (code "70") (name "Net-(LED12C-C)") (class "Default")
      (node (ref "LED12") (pin "5") (pinfunction "C_5") (pintype "passive"))
      (node (ref "R35") (pin "1") (pinfunction "1_1") (pintype "passive"))
    )
    (net (code "71") (name "Net-(LED13A-C)") (class "Default")
      (node (ref "LED13") (pin "4") (pinfunction "C_4") (pintype "passive"))
      (node (ref "R37") (pin "1") (pinfunction "1_1") (pintype "passive"))
    )
    (net (code "72") (name "Net-(LED13B-C)") (class "Default")
      (node (ref "LED13") (pin "6") (pinfunction "C_6") (pintype "passive"))
      (node (ref "R39") (pin "1") (pinfunction "1_1") (pintype "passive"))
    )
    (net (code "73") (name "Net-(LED13C-C)") (class "Default")
      (node (ref "LED13") (pin "5") (pinfunction "C_5") (pintype "passive"))
      (node (ref "R38") (pin "1") (pinfunction "1_1") (pintype "passive"))
    )
    (net (code "74") (name "Net-(LED14A-C)") (class "Default")
      (node (ref "LED14") (pin "4") (pinfunction "C_4") (pintype "passive"))
      (node (ref "R40") (pin "1") (pinfunction "1_1") (pintype "passive"))
    )
    (net (code "75") (name "Net-(LED14B-C)") (class "Default")
      (node (ref "LED14") (pin "6") (pinfunction "C_6") (pintype "passive"))
      (node (ref "R42") (pin "1") (pinfunction "1_1") (pintype "passive"))
    )
    (net (code "76") (name "Net-(LED14C-C)") (class "Default")
      (node (ref "LED14") (pin "5") (pinfunction "C_5") (pintype "passive"))
      (node (ref "R41") (pin "1") (pinfunction "1_1") (pintype "passive"))
    )
    (net (code "77") (name "Net-(LED15A-C)") (class "Default")
      (node (ref "LED15") (pin "4") (pinfunction "C_4") (pintype "passive"))
      (node (ref "R43") (pin "1") (pinfunction "1_1") (pintype "passive"))
    )
    (net (code "78") (name "Net-(LED15B-C)") (class "Default")
      (node (ref "LED15") (pin "6") (pinfunction "C_6") (pintype "passive"))
      (node (ref "R45") (pin "1") (pinfunction "1_1") (pintype "passive"))
    )
    (net (code "79") (name "Net-(LED15C-C)") (class "Default")
      (node (ref "LED15") (pin "5") (pinfunction "C_5") (pintype "passive"))
      (node (ref "R44") (pin "1") (pinfunction "1_1") (pintype "passive"))
    )
    (net (code "80") (name "Net-(LED16A-C)") (class "Default")
      (node (ref "LED16") (pin "4") (pinfunction "C_4") (pintype "passive"))
      (node (ref "R46") (pin "1") (pinfunction "1_1") (pintype "passive"))
    )
    (net (code "81") (name "Net-(LED16B-C)") (class "Default")
      (node (ref "LED16") (pin "6") (pinfunction "C_6") (pintype "passive"))
      (node (ref "R48") (pin "1") (pinfunction "1_1") (pintype "passive"))
    )
    (net (code "82") (name "Net-(LED16C-C)") (class "Default")
      (node (ref "LED16") (pin "5") (pinfunction "C_5") (pintype "passive"))
      (node (ref "R47") (pin "1") (pinfunction "1_1") (pintype "passive"))
    )
    (net (code "83") (name "unconnected-(LED1-PadTH)") (class "Default")
      (node (ref "LED1") (pin "TH") (pinfunction "TH_TH") (pintype "passive"))
    )
    (net (code "84") (name "unconnected-(LED2-PadTH)") (class "Default")
      (node (ref "LED2") (pin "TH") (pinfunction "TH_TH") (pintype "passive"))
    )
    (net (code "85") (name "unconnected-(LED3-PadTH)") (class "Default")
      (node (ref "LED3") (pin "TH") (pinfunction "TH_TH") (pintype "passive"))
    )
    (net (code "86") (name "unconnected-(LED4-PadTH)") (class "Default")
      (node (ref "LED4") (pin "TH") (pinfunction "TH_TH") (pintype "passive"))
    )
    (net (code "87") (name "unconnected-(LED5-PadTH)") (class "Default")
      (node (ref "LED5") (pin "TH") (pinfunction "TH_TH") (pintype "passive"))
    )
    (net (code "88") (name "unconnected-(LED6-PadTH)") (class "Default")
      (node (ref "LED6") (pin "TH") (pinfunction "TH_TH") (pintype "passive"))
    )
    (net (code "89") (name "unconnected-(LED7-PadTH)") (class "Default")
      (node (ref "LED7") (pin "TH") (pinfunction "TH_TH") (pintype "passive"))
    )
    (net (code "90") (name "unconnected-(LED8-PadTH)") (class "Default")
      (node (ref "LED8") (pin "TH") (pinfunction "TH_TH") (pintype "passive"))
    )
    (net (code "91") (name "unconnected-(LED9-PadTH)") (class "Default")
      (node (ref "LED9") (pin "TH") (pinfunction "TH_TH") (pintype "passive"))
    )
    (net (code "92") (name "unconnected-(LED10-PadTH)") (class "Default")
      (node (ref "LED10") (pin "TH") (pinfunction "TH_TH") (pintype "passive"))
    )
    (net (code "93") (name "unconnected-(LED11-PadTH)") (class "Default")
      (node (ref "LED11") (pin "TH") (pinfunction "TH_TH") (pintype "passive"))
    )
    (net (code "94") (name "unconnected-(LED12-PadTH)") (class "Default")
      (node (ref "LED12") (pin "TH") (pinfunction "TH_TH") (pintype "passive"))
    )
    (net (code "95") (name "unconnected-(LED13-PadTH)") (class "Default")
      (node (ref "LED13") (pin "TH") (pinfunction "TH_TH") (pintype "passive"))
    )
    (net (code "96") (name "unconnected-(LED14-PadTH)") (class "Default")
      (node (ref "LED14") (pin "TH") (pinfunction "TH_TH") (pintype "passive"))
    )
    (net (code "97") (name "unconnected-(LED15-PadTH)") (class "Default")
      (node (ref "LED15") (pin "TH") (pinfunction "TH_TH") (pintype "passive"))
    )
    (net (code "98") (name "unconnected-(LED16-PadTH)") (class "Default")
      (node (ref "LED16") (pin "TH") (pinfunction "TH_TH") (pintype "passive"))
    )
    (net (code "99") (name "unconnected-(SV1-Pad19)") (class "Default")
      (node (ref "SV1") (pin "19") (pinfunction "19_19") (pintype "passive"))
    )
    (net (code "100") (name "unconnected-(SV1-Pad20)") (class "Default")
      (node (ref "SV1") (pin "20") (pinfunction "20_20") (pintype "passive"))
    )
  )
)
